# nanino7.net
KiCad netlist of a schematic drawn in EAGLE
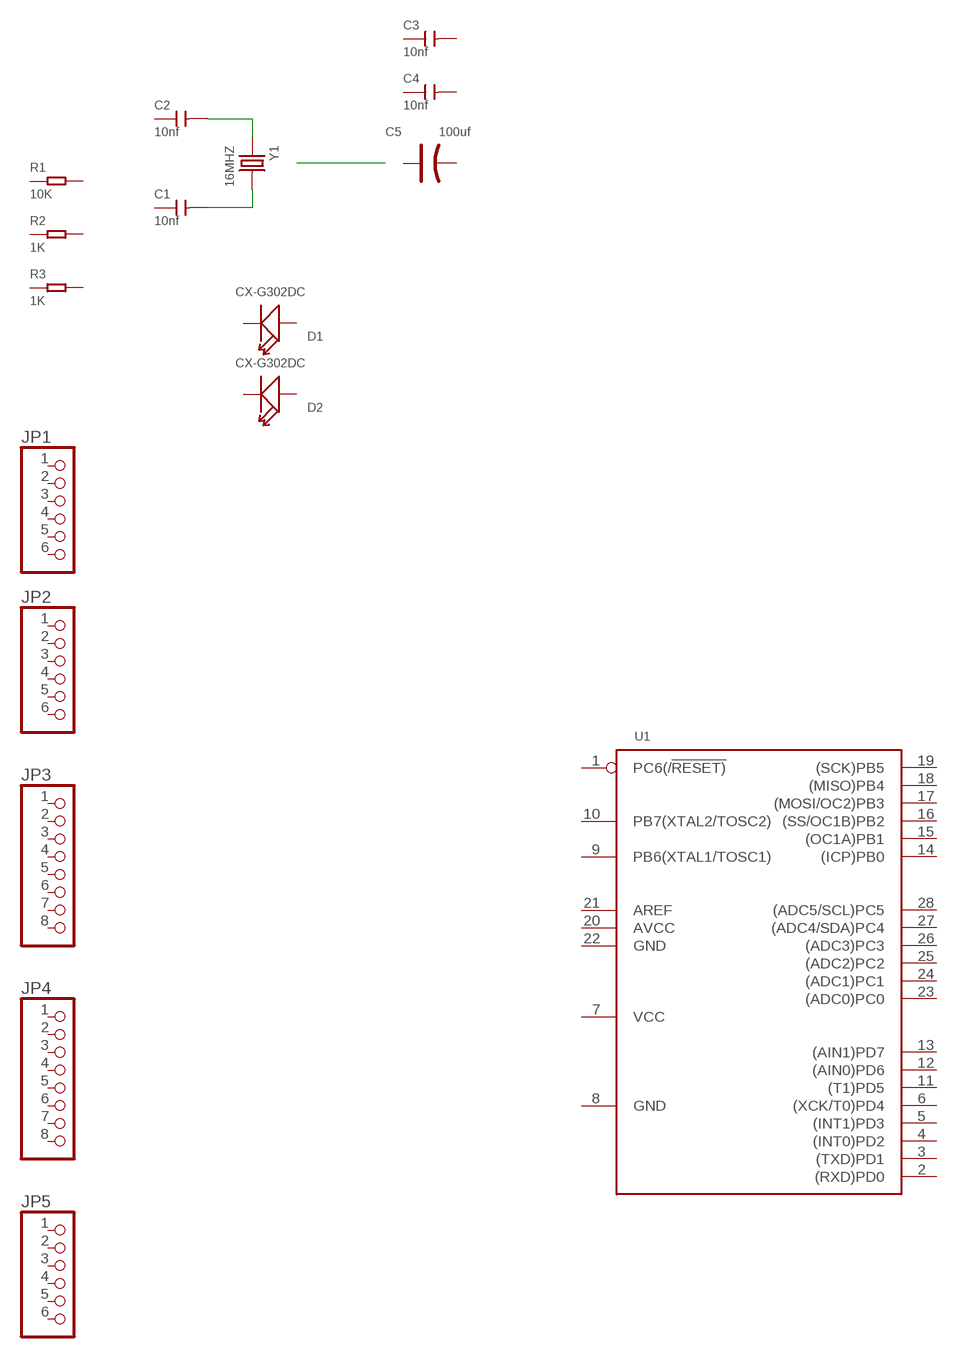
[diagram p0: schematic, sheet 1]

(export (version "E")
  (design (tool "Eeschema 10.0.6"))
  (components
    (comp (ref "C1")
      (value "10nf")
      (footprint "eagle-import:CERAMIC-2.54")
      (libsource (lib "eagle-import") (part "DIP-CERAMIC-DISC-10NF-50V-Y5V(D4.0MM)"))
    )
    (comp (ref "C2")
      (value "10nf")
      (footprint "eagle-import:CERAMIC-2.54")
      (libsource (lib "eagle-import") (part "DIP-CERAMIC-DISC-10NF-50V-Y5V(D4.0MM)"))
    )
    (comp (ref "C3")
      (value "10nf")
      (footprint "eagle-import:CERAMIC-2.54")
      (libsource (lib "eagle-import") (part "DIP-CERAMIC-DISC-10NF-50V-Y5V(D4.0MM)"))
    )
    (comp (ref "C4")
      (value "10nf")
      (footprint "eagle-import:CERAMIC-2.54")
      (libsource (lib "eagle-import") (part "DIP-CERAMIC-DISC-10NF-50V-Y5V(D4.0MM)"))
    )
    (comp (ref "C5")
      (value "100uf")
      (footprint "eagle-import:PC-D5.3MM")
      (fields (field (name "MPN") "KS 100uF/16V"))
      (libsource (lib "eagle-import") (part "DIP-ALUMINUM-47UF-16V(D5-H7MM)"))
    )
    (comp (ref "D1")
      (value "CX-G302DC")
      (footprint "eagle-import:LED2-2.54-D3.0MM")
      (libsource (lib "eagle-import") (part "DIP-LED-GREEN-GREEN(2P-D3MM)"))
    )
    (comp (ref "D2")
      (value "CX-G302DC")
      (footprint "eagle-import:LED2-2.54-D3.0MM")
      (libsource (lib "eagle-import") (part "DIP-LED-GREEN-GREEN(2P-D3MM)"))
    )
    (comp (ref "JP1")
      (value "PINHD-1X6")
      (footprint "eagle-import:1X06")
      (libsource (lib "eagle-import") (part "PINHD-1X6"))
    )
    (comp (ref "JP2")
      (value "PINHD-1X6")
      (footprint "eagle-import:1X06")
      (libsource (lib "eagle-import") (part "PINHD-1X6"))
    )
    (comp (ref "JP3")
      (value "PINHD-1X8")
      (footprint "eagle-import:1X08")
      (libsource (lib "eagle-import") (part "PINHD-1X8"))
    )
    (comp (ref "JP4")
      (value "PINHD-1X8")
      (footprint "eagle-import:1X08")
      (libsource (lib "eagle-import") (part "PINHD-1X8"))
    )
    (comp (ref "JP5")
      (value "PINHD-1X6")
      (footprint "eagle-import:1X06")
      (libsource (lib "eagle-import") (part "PINHD-1X6"))
    )
    (comp (ref "R1")
      (value "10K")
      (footprint "eagle-import:PR-D2.3XL6.5MM")
      (fields (field (name "MPN") "FHCFR-1/4W-103J"))
      (libsource (lib "eagle-import") (part "DIP-RES-10K-5%-1/4W(PR-D2.3XL6.5MM)"))
    )
    (comp (ref "R2")
      (value "1K")
      (footprint "eagle-import:PR-D2.3XL6.5MM")
      (fields (field (name "MPN") "FHCFR-1/4W-102J"))
      (libsource (lib "eagle-import") (part "DIP-RES-1K-5%-1/4W(PR-D2.3XL6.5MM)"))
    )
    (comp (ref "R3")
      (value "1K")
      (footprint "eagle-import:PR-D2.3XL6.5MM")
      (fields (field (name "MPN") "FHCFR-1/4W-102J"))
      (libsource (lib "eagle-import") (part "DIP-RES-1K-5%-1/4W(PR-D2.3XL6.5MM)"))
    )
    (comp (ref "U1")
      (value "MCU-ATMEGA328P-PU(DIP28)")
      (footprint "eagle-import:DIP28-2.54-34.7X7.62MM")
      (fields (field (name "MPN") "ATMEGA328P-PU"))
      (libsource (lib "eagle-import") (part "MCU-ATMEGA328P-PU(DIP28)"))
    )
    (comp (ref "Y1")
      (value "16MHZ")
      (footprint "eagle-import:HC49US")
      (fields (field (name "MPN") "HC-49US    16.000MHz"))
      (libsource (lib "eagle-import") (part "DIP-CRYSTAL-16MHZ-18PF-30PPM-40R(HC49US)"))
    )
  )
  (nets
    (net (code "1") (name "Net-(C1-Pad2)") (class "Default")
      (node (ref "C1") (pin "2") (pinfunction "2_2") (pintype "passive"))
      (node (ref "Y1") (pin "2") (pinfunction "2_2") (pintype "passive"))
    )
    (net (code "2") (name "Net-(C2-Pad2)") (class "Default")
      (node (ref "C2") (pin "2") (pinfunction "2_2") (pintype "passive"))
      (node (ref "Y1") (pin "1") (pinfunction "1_1") (pintype "passive"))
    )
    (net (code "3") (name "unconnected-(C1-Pad1)") (class "Default")
      (node (ref "C1") (pin "1") (pinfunction "1_1") (pintype "passive"))
    )
    (net (code "4") (name "unconnected-(C2-Pad1)") (class "Default")
      (node (ref "C2") (pin "1") (pinfunction "1_1") (pintype "passive"))
    )
    (net (code "5") (name "unconnected-(C3-Pad1)") (class "Default")
      (node (ref "C3") (pin "1") (pinfunction "1_1") (pintype "passive"))
    )
    (net (code "6") (name "unconnected-(C3-Pad2)") (class "Default")
      (node (ref "C3") (pin "2") (pinfunction "2_2") (pintype "passive"))
    )
    (net (code "7") (name "unconnected-(C4-Pad1)") (class "Default")
      (node (ref "C4") (pin "1") (pinfunction "1_1") (pintype "passive"))
    )
    (net (code "8") (name "unconnected-(C4-Pad2)") (class "Default")
      (node (ref "C4") (pin "2") (pinfunction "2_2") (pintype "passive"))
    )
    (net (code "9") (name "unconnected-(C5-Pad+)") (class "Default")
      (node (ref "C5") (pin "+") (pinfunction "+_+") (pintype "passive"))
    )
    (net (code "10") (name "unconnected-(C5-Pad-)") (class "Default")
      (node (ref "C5") (pin "-") (pinfunction "-_-") (pintype "passive"))
    )
    (net (code "11") (name "unconnected-(D1-+-PadA)") (class "Default")
      (node (ref "D1") (pin "A") (pinfunction "+_A") (pintype "passive"))
    )
    (net (code "12") (name "unconnected-(D1---PadK)") (class "Default")
      (node (ref "D1") (pin "K") (pinfunction "-_K") (pintype "passive"))
    )
    (net (code "13") (name "unconnected-(D2-+-PadA)") (class "Default")
      (node (ref "D2") (pin "A") (pinfunction "+_A") (pintype "passive"))
    )
    (net (code "14") (name "unconnected-(D2---PadK)") (class "Default")
      (node (ref "D2") (pin "K") (pinfunction "-_K") (pintype "passive"))
    )
    (net (code "15") (name "unconnected-(JP1-Pad1)") (class "Default")
      (node (ref "JP1") (pin "1") (pinfunction "1_1") (pintype "passive"))
    )
    (net (code "16") (name "unconnected-(JP1-Pad2)") (class "Default")
      (node (ref "JP1") (pin "2") (pinfunction "2_2") (pintype "passive"))
    )
    (net (code "17") (name "unconnected-(JP1-Pad3)") (class "Default")
      (node (ref "JP1") (pin "3") (pinfunction "3_3") (pintype "passive"))
    )
    (net (code "18") (name "unconnected-(JP1-Pad4)") (class "Default")
      (node (ref "JP1") (pin "4") (pinfunction "4_4") (pintype "passive"))
    )
    (net (code "19") (name "unconnected-(JP1-Pad5)") (class "Default")
      (node (ref "JP1") (pin "5") (pinfunction "5_5") (pintype "passive"))
    )
    (net (code "20") (name "unconnected-(JP1-Pad6)") (class "Default")
      (node (ref "JP1") (pin "6") (pinfunction "6_6") (pintype "passive"))
    )
    (net (code "21") (name "unconnected-(JP2-Pad1)") (class "Default")
      (node (ref "JP2") (pin "1") (pinfunction "1_1") (pintype "passive"))
    )
    (net (code "22") (name "unconnected-(JP2-Pad2)") (class "Default")
      (node (ref "JP2") (pin "2") (pinfunction "2_2") (pintype "passive"))
    )
    (net (code "23") (name "unconnected-(JP2-Pad3)") (class "Default")
      (node (ref "JP2") (pin "3") (pinfunction "3_3") (pintype "passive"))
    )
    (net (code "24") (name "unconnected-(JP2-Pad4)") (class "Default")
      (node (ref "JP2") (pin "4") (pinfunction "4_4") (pintype "passive"))
    )
    (net (code "25") (name "unconnected-(JP2-Pad5)") (class "Default")
      (node (ref "JP2") (pin "5") (pinfunction "5_5") (pintype "passive"))
    )
    (net (code "26") (name "unconnected-(JP2-Pad6)") (class "Default")
      (node (ref "JP2") (pin "6") (pinfunction "6_6") (pintype "passive"))
    )
    (net (code "27") (name "unconnected-(JP3-Pad1)") (class "Default")
      (node (ref "JP3") (pin "1") (pinfunction "1_1") (pintype "passive"))
    )
    (net (code "28") (name "unconnected-(JP3-Pad2)") (class "Default")
      (node (ref "JP3") (pin "2") (pinfunction "2_2") (pintype "passive"))
    )
    (net (code "29") (name "unconnected-(JP3-Pad3)") (class "Default")
      (node (ref "JP3") (pin "3") (pinfunction "3_3") (pintype "passive"))
    )
    (net (code "30") (name "unconnected-(JP3-Pad4)") (class "Default")
      (node (ref "JP3") (pin "4") (pinfunction "4_4") (pintype "passive"))
    )
    (net (code "31") (name "unconnected-(JP3-Pad5)") (class "Default")
      (node (ref "JP3") (pin "5") (pinfunction "5_5") (pintype "passive"))
    )
    (net (code "32") (name "unconnected-(JP3-Pad6)") (class "Default")
      (node (ref "JP3") (pin "6") (pinfunction "6_6") (pintype "passive"))
    )
    (net (code "33") (name "unconnected-(JP3-Pad7)") (class "Default")
      (node (ref "JP3") (pin "7") (pinfunction "7_7") (pintype "passive"))
    )
    (net (code "34") (name "unconnected-(JP3-Pad8)") (class "Default")
      (node (ref "JP3") (pin "8") (pinfunction "8_8") (pintype "passive"))
    )
    (net (code "35") (name "unconnected-(JP4-Pad1)") (class "Default")
      (node (ref "JP4") (pin "1") (pinfunction "1_1") (pintype "passive"))
    )
    (net (code "36") (name "unconnected-(JP4-Pad2)") (class "Default")
      (node (ref "JP4") (pin "2") (pinfunction "2_2") (pintype "passive"))
    )
    (net (code "37") (name "unconnected-(JP4-Pad3)") (class "Default")
      (node (ref "JP4") (pin "3") (pinfunction "3_3") (pintype "passive"))
    )
    (net (code "38") (name "unconnected-(JP4-Pad4)") (class "Default")
      (node (ref "JP4") (pin "4") (pinfunction "4_4") (pintype "passive"))
    )
    (net (code "39") (name "unconnected-(JP4-Pad5)") (class "Default")
      (node (ref "JP4") (pin "5") (pinfunction "5_5") (pintype "passive"))
    )
    (net (code "40") (name "unconnected-(JP4-Pad6)") (class "Default")
      (node (ref "JP4") (pin "6") (pinfunction "6_6") (pintype "passive"))
    )
    (net (code "41") (name "unconnected-(JP4-Pad7)") (class "Default")
      (node (ref "JP4") (pin "7") (pinfunction "7_7") (pintype "passive"))
    )
    (net (code "42") (name "unconnected-(JP4-Pad8)") (class "Default")
      (node (ref "JP4") (pin "8") (pinfunction "8_8") (pintype "passive"))
    )
    (net (code "43") (name "unconnected-(JP5-Pad1)") (class "Default")
      (node (ref "JP5") (pin "1") (pinfunction "1_1") (pintype "passive"))
    )
    (net (code "44") (name "unconnected-(JP5-Pad2)") (class "Default")
      (node (ref "JP5") (pin "2") (pinfunction "2_2") (pintype "passive"))
    )
    (net (code "45") (name "unconnected-(JP5-Pad3)") (class "Default")
      (node (ref "JP5") (pin "3") (pinfunction "3_3") (pintype "passive"))
    )
    (net (code "46") (name "unconnected-(JP5-Pad4)") (class "Default")
      (node (ref "JP5") (pin "4") (pinfunction "4_4") (pintype "passive"))
    )
    (net (code "47") (name "unconnected-(JP5-Pad5)") (class "Default")
      (node (ref "JP5") (pin "5") (pinfunction "5_5") (pintype "passive"))
    )
    (net (code "48") (name "unconnected-(JP5-Pad6)") (class "Default")
      (node (ref "JP5") (pin "6") (pinfunction "6_6") (pintype "passive"))
    )
    (net (code "49") (name "unconnected-(R1-Pad1)") (class "Default")
      (node (ref "R1") (pin "1") (pinfunction "1_1") (pintype "passive"))
    )
    (net (code "50") (name "unconnected-(R1-Pad2)") (class "Default")
      (node (ref "R1") (pin "2") (pinfunction "2_2") (pintype "passive"))
    )
    (net (code "51") (name "unconnected-(R2-Pad1)") (class "Default")
      (node (ref "R2") (pin "1") (pinfunction "1_1") (pintype "passive"))
    )
    (net (code "52") (name "unconnected-(R2-Pad2)") (class "Default")
      (node (ref "R2") (pin "2") (pinfunction "2_2") (pintype "passive"))
    )
    (net (code "53") (name "unconnected-(R3-Pad1)") (class "Default")
      (node (ref "R3") (pin "1") (pinfunction "1_1") (pintype "passive"))
    )
    (net (code "54") (name "unconnected-(R3-Pad2)") (class "Default")
      (node (ref "R3") (pin "2") (pinfunction "2_2") (pintype "passive"))
    )
    (net (code "55") (name "unconnected-(U1-(ADC0)PC0-Pad23)") (class "Default")
      (node (ref "U1") (pin "23") (pinfunction "(ADC0)PC0_23") (pintype "bidirectional"))
    )
    (net (code "56") (name "unconnected-(U1-(ADC1)PC1-Pad24)") (class "Default")
      (node (ref "U1") (pin "24") (pinfunction "(ADC1)PC1_24") (pintype "bidirectional"))
    )
    (net (code "57") (name "unconnected-(U1-(ADC2)PC2-Pad25)") (class "Default")
      (node (ref "U1") (pin "25") (pinfunction "(ADC2)PC2_25") (pintype "bidirectional"))
    )
    (net (code "58") (name "unconnected-(U1-(ADC3)PC3-Pad26)") (class "Default")
      (node (ref "U1") (pin "26") (pinfunction "(ADC3)PC3_26") (pintype "bidirectional"))
    )
    (net (code "59") (name "unconnected-(U1-(ADC4{slash}SDA)PC4-Pad27)") (class "Default")
      (node (ref "U1") (pin "27") (pinfunction "(ADC4/SDA)PC4_27") (pintype "bidirectional"))
    )
    (net (code "60") (name "unconnected-(U1-(ADC5{slash}SCL)PC5-Pad28)") (class "Default")
      (node (ref "U1") (pin "28") (pinfunction "(ADC5/SCL)PC5_28") (pintype "bidirectional"))
    )
    (net (code "61") (name "unconnected-(U1-(AIN0)PD6-Pad12)") (class "Default")
      (node (ref "U1") (pin "12") (pinfunction "(AIN0)PD6_12") (pintype "bidirectional"))
    )
    (net (code "62") (name "unconnected-(U1-(AIN1)PD7-Pad13)") (class "Default")
      (node (ref "U1") (pin "13") (pinfunction "(AIN1)PD7_13") (pintype "bidirectional"))
    )
    (net (code "63") (name "unconnected-(U1-(ICP)PB0-Pad14)") (class "Default")
      (node (ref "U1") (pin "14") (pinfunction "(ICP)PB0_14") (pintype "bidirectional"))
    )
    (net (code "64") (name "unconnected-(U1-(INT0)PD2-Pad4)") (class "Default")
      (node (ref "U1") (pin "4") (pinfunction "(INT0)PD2_4") (pintype "bidirectional"))
    )
    (net (code "65") (name "unconnected-(U1-(INT1)PD3-Pad5)") (class "Default")
      (node (ref "U1") (pin "5") (pinfunction "(INT1)PD3_5") (pintype "bidirectional"))
    )
    (net (code "66") (name "unconnected-(U1-(MISO)PB4-Pad18)") (class "Default")
      (node (ref "U1") (pin "18") (pinfunction "(MISO)PB4_18") (pintype "bidirectional"))
    )
    (net (code "67") (name "unconnected-(U1-(MOSI{slash}OC2)PB3-Pad17)") (class "Default")
      (node (ref "U1") (pin "17") (pinfunction "(MOSI/OC2)PB3_17") (pintype "bidirectional"))
    )
    (net (code "68") (name "unconnected-(U1-(OC1A)PB1-Pad15)") (class "Default")
      (node (ref "U1") (pin "15") (pinfunction "(OC1A)PB1_15") (pintype "bidirectional"))
    )
    (net (code "69") (name "unconnected-(U1-(RXD)PD0-Pad2)") (class "Default")
      (node (ref "U1") (pin "2") (pinfunction "(RXD)PD0_2") (pintype "bidirectional"))
    )
    (net (code "70") (name "unconnected-(U1-(SCK)PB5-Pad19)") (class "Default")
      (node (ref "U1") (pin "19") (pinfunction "(SCK)PB5_19") (pintype "bidirectional"))
    )
    (net (code "71") (name "unconnected-(U1-(SS{slash}OC1B)PB2-Pad16)") (class "Default")
      (node (ref "U1") (pin "16") (pinfunction "(SS/OC1B)PB2_16") (pintype "bidirectional"))
    )
    (net (code "72") (name "unconnected-(U1-(T1)PD5-Pad11)") (class "Default")
      (node (ref "U1") (pin "11") (pinfunction "(T1)PD5_11") (pintype "bidirectional"))
    )
    (net (code "73") (name "unconnected-(U1-(TXD)PD1-Pad3)") (class "Default")
      (node (ref "U1") (pin "3") (pinfunction "(TXD)PD1_3") (pintype "bidirectional"))
    )
    (net (code "74") (name "unconnected-(U1-(XCK{slash}T0)PD4-Pad6)") (class "Default")
      (node (ref "U1") (pin "6") (pinfunction "(XCK/T0)PD4_6") (pintype "bidirectional"))
    )
    (net (code "75") (name "unconnected-(U1-AREF-Pad21)") (class "Default")
      (node (ref "U1") (pin "21") (pinfunction "AREF_21") (pintype "bidirectional"))
    )
    (net (code "76") (name "unconnected-(U1-AVCC-Pad20)") (class "Default")
      (node (ref "U1") (pin "20") (pinfunction "AVCC_20") (pintype "bidirectional"))
    )
    (net (code "77") (name "unconnected-(U1-GND-Pad8)") (class "Default")
      (node (ref "U1") (pin "8") (pinfunction "GND_8") (pintype "bidirectional"))
    )
    (net (code "78") (name "unconnected-(U1-GND-Pad22)") (class "Default")
      (node (ref "U1") (pin "22") (pinfunction "GND_22") (pintype "bidirectional"))
    )
    (net (code "79") (name "unconnected-(U1-PB6(XTAL1{slash}TOSC1)-Pad9)") (class "Default")
      (node (ref "U1") (pin "9") (pinfunction "PB6(XTAL1/TOSC1)_9") (pintype "bidirectional"))
    )
    (net (code "80") (name "unconnected-(U1-PB7(XTAL2{slash}TOSC2)-Pad10)") (class "Default")
      (node (ref "U1") (pin "10") (pinfunction "PB7(XTAL2/TOSC2)_10") (pintype "bidirectional"))
    )
    (net (code "81") (name "unconnected-(U1-PC6({slash}~{RESET})-Pad1)") (class "Default")
      (node (ref "U1") (pin "1") (pinfunction "PC6(/~{RESET})_1") (pintype "bidirectional"))
    )
    (net (code "82") (name "unconnected-(U1-VCC-Pad7)") (class "Default")
      (node (ref "U1") (pin "7") (pinfunction "VCC_7") (pintype "bidirectional"))
    )
  )
)
